# PIC18_Peripheral_breakout_LRbuttons.net
KiCad netlist of a schematic drawn in EAGLE
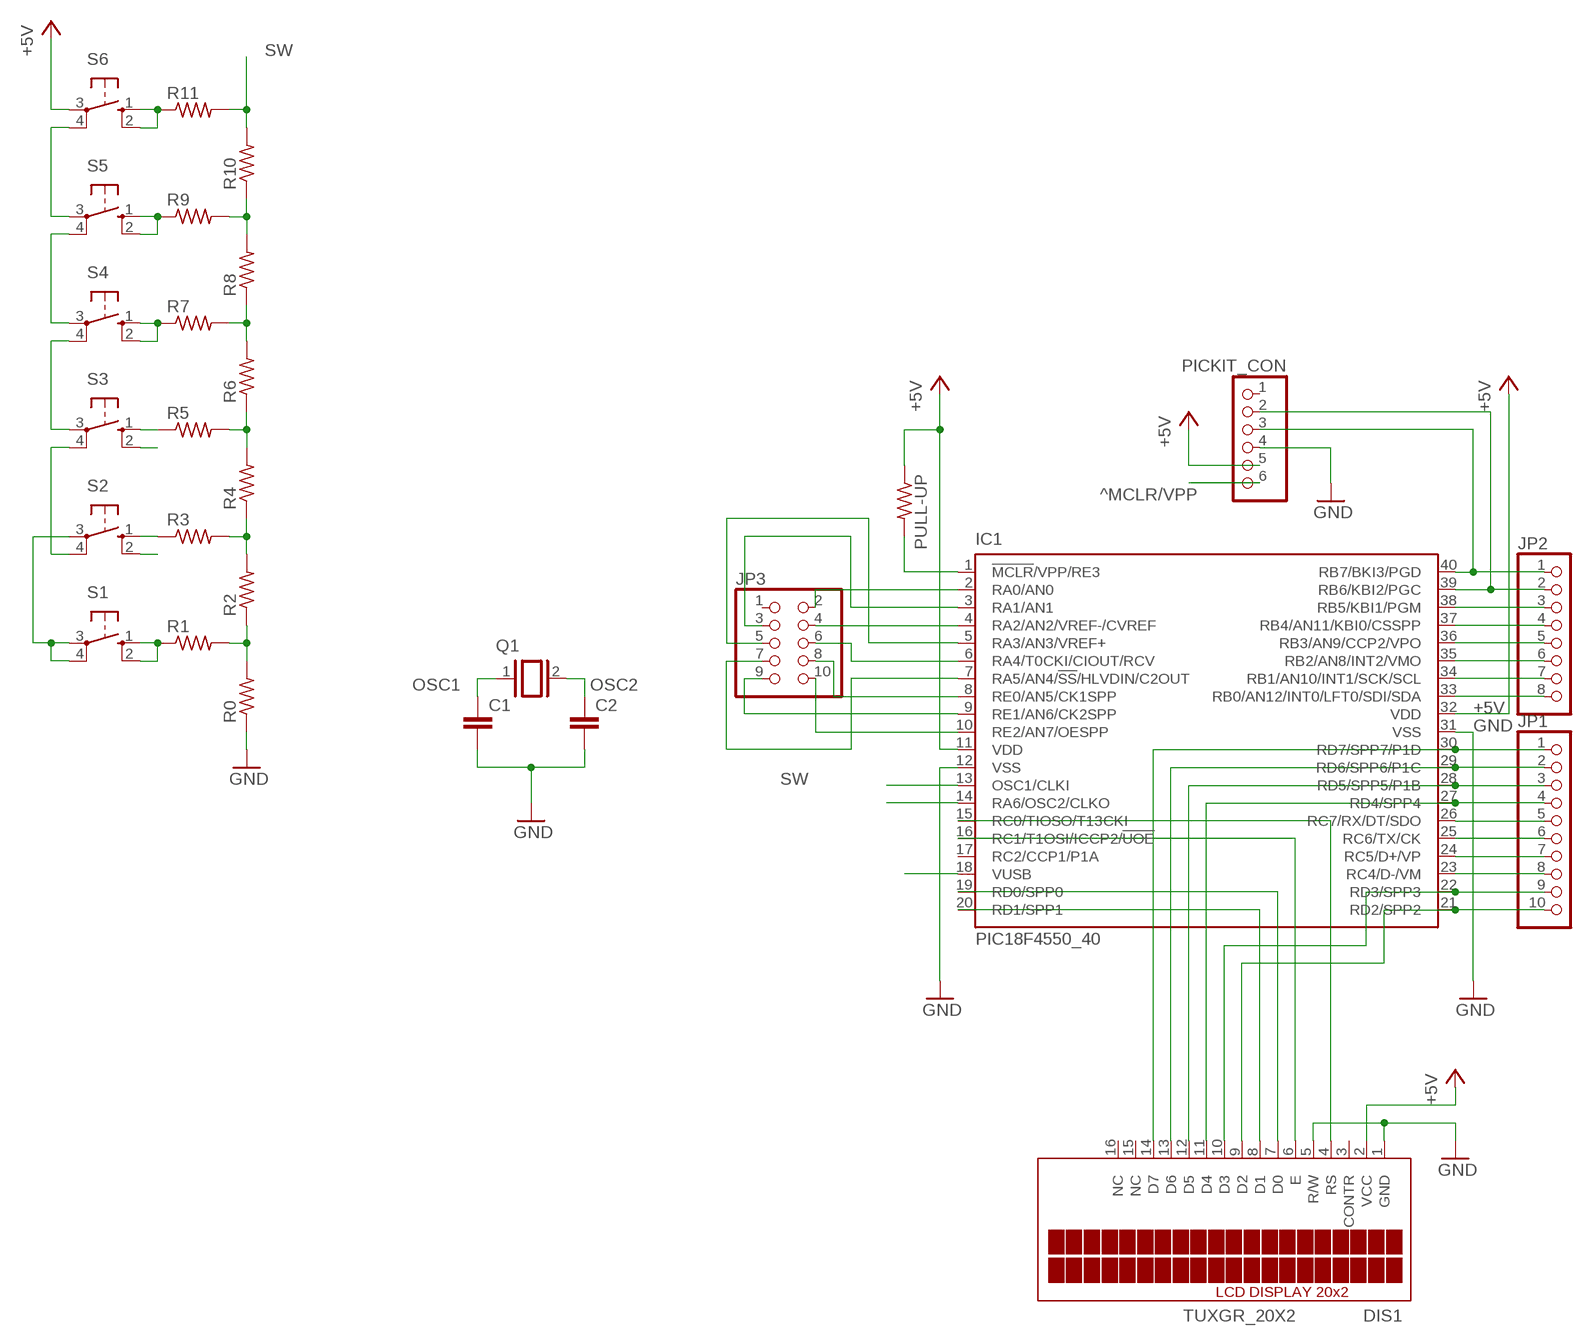
[diagram p0: schematic, sheet 1]

(export (version "E")
  (design (tool "Eeschema 10.0.6"))
  (components
    (comp (ref "C1")
      (value "C-EUC1206")
      (footprint "eagle-import:C1206")
      (libsource (lib "eagle-import") (part "C-EUC1206"))
    )
    (comp (ref "C2")
      (value "C-EUC1206")
      (footprint "eagle-import:C1206")
      (libsource (lib "eagle-import") (part "C-EUC1206"))
    )
    (comp (ref "DIS1")
      (value "TUXGR_20X2")
      (footprint "eagle-import:TUXGR_20X2")
      (libsource (lib "eagle-import") (part "TUXGR_20X2"))
    )
    (comp (ref "IC1")
      (value "PIC18F4550_40")
      (footprint "eagle-import:DIL40")
      (fields (field (name "MF") "MICROCHIP") (field (name "MPN") "PIC18F4550-I/P"))
      (libsource (lib "eagle-import") (part "PIC18F4_40550"))
    )
    (comp (ref "JP1")
      (value "PINHD-1X10")
      (footprint "eagle-import:1X10")
      (libsource (lib "eagle-import") (part "PINHD-1X10"))
    )
    (comp (ref "JP2")
      (value "PINHD-1X8")
      (footprint "eagle-import:1X08")
      (libsource (lib "eagle-import") (part "PINHD-1X8"))
    )
    (comp (ref "JP3")
      (value "PINHD-2X5")
      (footprint "eagle-import:2X05")
      (libsource (lib "eagle-import") (part "PINHD-2X5"))
    )
    (comp (ref "PICKIT_CON")
      (value "PINHD-1X6/90")
      (footprint "eagle-import:1X06_90")
      (libsource (lib "eagle-import") (part "PINHD-1X6/90"))
    )
    (comp (ref "PULL-UP")
      (value "R-US_R1206")
      (footprint "eagle-import:R1206")
      (libsource (lib "eagle-import") (part "R-US_R1206"))
    )
    (comp (ref "Q1")
      (value "XTAL/S")
      (footprint "eagle-import:QS")
      (libsource (lib "eagle-import") (part "XTAL/S"))
    )
    (comp (ref "R0")
      (value "R-US_R1206")
      (footprint "eagle-import:R1206")
      (libsource (lib "eagle-import") (part "R-US_R1206"))
    )
    (comp (ref "R1")
      (value "R-US_R1206")
      (footprint "eagle-import:R1206")
      (libsource (lib "eagle-import") (part "R-US_R1206"))
    )
    (comp (ref "R2")
      (value "R-US_R1206")
      (footprint "eagle-import:R1206")
      (libsource (lib "eagle-import") (part "R-US_R1206"))
    )
    (comp (ref "R3")
      (value "R-US_R1206")
      (footprint "eagle-import:R1206")
      (libsource (lib "eagle-import") (part "R-US_R1206"))
    )
    (comp (ref "R4")
      (value "R-US_R1206")
      (footprint "eagle-import:R1206")
      (libsource (lib "eagle-import") (part "R-US_R1206"))
    )
    (comp (ref "R5")
      (value "R-US_R1206")
      (footprint "eagle-import:R1206")
      (libsource (lib "eagle-import") (part "R-US_R1206"))
    )
    (comp (ref "R6")
      (value "R-US_R1206")
      (footprint "eagle-import:R1206")
      (libsource (lib "eagle-import") (part "R-US_R1206"))
    )
    (comp (ref "R7")
      (value "R-US_R1206")
      (footprint "eagle-import:R1206")
      (libsource (lib "eagle-import") (part "R-US_R1206"))
    )
    (comp (ref "R8")
      (value "R-US_R1206")
      (footprint "eagle-import:R1206")
      (libsource (lib "eagle-import") (part "R-US_R1206"))
    )
    (comp (ref "R9")
      (value "R-US_R1206")
      (footprint "eagle-import:R1206")
      (libsource (lib "eagle-import") (part "R-US_R1206"))
    )
    (comp (ref "R10")
      (value "R-US_R1206")
      (footprint "eagle-import:R1206")
      (libsource (lib "eagle-import") (part "R-US_R1206"))
    )
    (comp (ref "R11")
      (value "R-US_R1206")
      (footprint "eagle-import:R1206")
      (libsource (lib "eagle-import") (part "R-US_R1206"))
    )
    (comp (ref "S1")
      (value "10-XX")
      (footprint "eagle-import:B3F-10XX")
      (fields (field (name "MPN") "B3F-1000"))
      (libsource (lib "eagle-import") (part "10-XX"))
    )
    (comp (ref "S2")
      (value "10-XX")
      (footprint "eagle-import:B3F-10XX")
      (fields (field (name "MPN") "B3F-1000"))
      (libsource (lib "eagle-import") (part "10-XX"))
    )
    (comp (ref "S3")
      (value "10-XX")
      (footprint "eagle-import:B3F-10XX")
      (fields (field (name "MPN") "B3F-1000"))
      (libsource (lib "eagle-import") (part "10-XX"))
    )
    (comp (ref "S4")
      (value "10-XX")
      (footprint "eagle-import:B3F-10XX")
      (fields (field (name "MPN") "B3F-1000"))
      (libsource (lib "eagle-import") (part "10-XX"))
    )
    (comp (ref "S5")
      (value "10-XX")
      (footprint "eagle-import:B3F-10XX")
      (fields (field (name "MPN") "B3F-1000"))
      (libsource (lib "eagle-import") (part "10-XX"))
    )
    (comp (ref "S6")
      (value "10-XX")
      (footprint "eagle-import:B3F-10XX")
      (fields (field (name "MPN") "B3F-1000"))
      (libsource (lib "eagle-import") (part "10-XX"))
    )
  )
  (nets
    (net (code "1") (name "+5V") (class "Default")
      (node (ref "DIS1") (pin "2") (pinfunction "VCC_2") (pintype "power_in"))
      (node (ref "IC1") (pin "11") (pinfunction "VDD_11") (pintype "power_in"))
      (node (ref "IC1") (pin "32") (pinfunction "VDD_32") (pintype "power_in"))
      (node (ref "PICKIT_CON") (pin "5") (pinfunction "5_5") (pintype "passive"))
      (node (ref "PULL-UP") (pin "1") (pinfunction "1_1") (pintype "passive"))
      (node (ref "S6") (pin "3") (pinfunction "P_3") (pintype "passive"))
    )
    (net (code "2") (name "/OSC1") (class "Default")
      (node (ref "C1") (pin "1") (pinfunction "1_1") (pintype "passive"))
      (node (ref "IC1") (pin "13") (pinfunction "OSC1/CLKI_13") (pintype "input"))
      (node (ref "Q1") (pin "1") (pinfunction "1_1") (pintype "passive"))
    )
    (net (code "3") (name "/OSC2") (class "Default")
      (node (ref "C2") (pin "1") (pinfunction "1_1") (pintype "passive"))
      (node (ref "IC1") (pin "14") (pinfunction "RA6/OSC2/CLKO_14") (pintype "output"))
      (node (ref "Q1") (pin "2") (pinfunction "2_2") (pintype "passive"))
    )
    (net (code "4") (name "/SW") (class "Default")
      (node (ref "IC1") (pin "10") (pinfunction "RE2/AN7/OESPP_10") (pintype "bidirectional"))
      (node (ref "JP3") (pin "10") (pinfunction "10_10") (pintype "passive"))
      (node (ref "R10") (pin "2") (pinfunction "2_2") (pintype "passive"))
      (node (ref "R11") (pin "2") (pinfunction "2_2") (pintype "passive"))
    )
    (net (code "5") (name "/^MCLR{slash}VPP") (class "Default")
      (node (ref "IC1") (pin "1") (pinfunction "~{MCLR}/VPP/RE3_1") (pintype "input"))
      (node (ref "PICKIT_CON") (pin "6") (pinfunction "6_6") (pintype "passive"))
      (node (ref "PULL-UP") (pin "2") (pinfunction "2_2") (pintype "passive"))
    )
    (net (code "6") (name "GND") (class "Default")
      (node (ref "C1") (pin "2") (pinfunction "2_2") (pintype "passive"))
      (node (ref "C2") (pin "2") (pinfunction "2_2") (pintype "passive"))
      (node (ref "DIS1") (pin "1") (pinfunction "GND_1") (pintype "power_in"))
      (node (ref "DIS1") (pin "5") (pinfunction "R/W_5") (pintype "input"))
      (node (ref "IC1") (pin "12") (pinfunction "VSS_12") (pintype "power_in"))
      (node (ref "IC1") (pin "31") (pinfunction "VSS_31") (pintype "power_in"))
      (node (ref "PICKIT_CON") (pin "4") (pinfunction "4_4") (pintype "passive"))
      (node (ref "R0") (pin "1") (pinfunction "1_1") (pintype "passive"))
    )
    (net (code "7") (name "Net-(DIS1-D0)") (class "Default")
      (node (ref "DIS1") (pin "7") (pinfunction "D0_7") (pintype "input"))
      (node (ref "IC1") (pin "19") (pinfunction "RD0/SPP0_19") (pintype "bidirectional"))
    )
    (net (code "8") (name "Net-(DIS1-D1)") (class "Default")
      (node (ref "DIS1") (pin "8") (pinfunction "D1_8") (pintype "input"))
      (node (ref "IC1") (pin "20") (pinfunction "RD1/SPP1_20") (pintype "bidirectional"))
    )
    (net (code "9") (name "Net-(DIS1-D2)") (class "Default")
      (node (ref "DIS1") (pin "9") (pinfunction "D2_9") (pintype "input"))
      (node (ref "IC1") (pin "21") (pinfunction "RD2/SPP2_21") (pintype "bidirectional"))
      (node (ref "JP1") (pin "10") (pinfunction "10_10") (pintype "passive"))
    )
    (net (code "10") (name "Net-(DIS1-D3)") (class "Default")
      (node (ref "DIS1") (pin "10") (pinfunction "D3_10") (pintype "input"))
      (node (ref "IC1") (pin "22") (pinfunction "RD3/SPP3_22") (pintype "bidirectional"))
      (node (ref "JP1") (pin "9") (pinfunction "9_9") (pintype "passive"))
    )
    (net (code "11") (name "Net-(DIS1-D4)") (class "Default")
      (node (ref "DIS1") (pin "11") (pinfunction "D4_11") (pintype "input"))
      (node (ref "IC1") (pin "27") (pinfunction "RD4/SPP4_27") (pintype "bidirectional"))
      (node (ref "JP1") (pin "4") (pinfunction "4_4") (pintype "passive"))
    )
    (net (code "12") (name "Net-(DIS1-D5)") (class "Default")
      (node (ref "DIS1") (pin "12") (pinfunction "D5_12") (pintype "input"))
      (node (ref "IC1") (pin "28") (pinfunction "RD5/SPP5/P1B_28") (pintype "bidirectional"))
      (node (ref "JP1") (pin "3") (pinfunction "3_3") (pintype "passive"))
    )
    (net (code "13") (name "Net-(DIS1-D6)") (class "Default")
      (node (ref "DIS1") (pin "13") (pinfunction "D6_13") (pintype "input"))
      (node (ref "IC1") (pin "29") (pinfunction "RD6/SPP6/P1C_29") (pintype "bidirectional"))
      (node (ref "JP1") (pin "2") (pinfunction "2_2") (pintype "passive"))
    )
    (net (code "14") (name "Net-(DIS1-D7)") (class "Default")
      (node (ref "DIS1") (pin "14") (pinfunction "D7_14") (pintype "input"))
      (node (ref "IC1") (pin "30") (pinfunction "RD7/SPP7/P1D_30") (pintype "bidirectional"))
      (node (ref "JP1") (pin "1") (pinfunction "1_1") (pintype "passive"))
    )
    (net (code "15") (name "Net-(DIS1-E)") (class "Default")
      (node (ref "DIS1") (pin "6") (pinfunction "E_6") (pintype "input"))
      (node (ref "IC1") (pin "16") (pinfunction "RC1/T1OSI/ICCP2/~{UOE}_16") (pintype "bidirectional"))
    )
    (net (code "16") (name "Net-(DIS1-RS)") (class "Default")
      (node (ref "DIS1") (pin "4") (pinfunction "RS_4") (pintype "input"))
      (node (ref "IC1") (pin "15") (pinfunction "RC0/TIOSO/T13CKI_15") (pintype "bidirectional"))
    )
    (net (code "17") (name "Net-(IC1-RA0{slash}AN0)") (class "Default")
      (node (ref "IC1") (pin "2") (pinfunction "RA0/AN0_2") (pintype "bidirectional"))
      (node (ref "JP3") (pin "2") (pinfunction "2_2") (pintype "passive"))
    )
    (net (code "18") (name "Net-(IC1-RA1{slash}AN1)") (class "Default")
      (node (ref "IC1") (pin "3") (pinfunction "RA1/AN1_3") (pintype "bidirectional"))
      (node (ref "JP3") (pin "3") (pinfunction "3_3") (pintype "passive"))
    )
    (net (code "19") (name "Net-(IC1-RA2{slash}AN2{slash}VREF-{slash}CVREF)") (class "Default")
      (node (ref "IC1") (pin "4") (pinfunction "RA2/AN2/VREF-/CVREF_4") (pintype "bidirectional"))
      (node (ref "JP3") (pin "4") (pinfunction "4_4") (pintype "passive"))
    )
    (net (code "20") (name "Net-(IC1-RA3{slash}AN3{slash}VREF+)") (class "Default")
      (node (ref "IC1") (pin "5") (pinfunction "RA3/AN3/VREF+_5") (pintype "bidirectional"))
      (node (ref "JP3") (pin "5") (pinfunction "5_5") (pintype "passive"))
    )
    (net (code "21") (name "Net-(IC1-RA4{slash}T0CKI{slash}CIOUT{slash}RCV)") (class "Default")
      (node (ref "IC1") (pin "6") (pinfunction "RA4/T0CKI/CIOUT/RCV_6") (pintype "bidirectional"))
      (node (ref "JP3") (pin "6") (pinfunction "6_6") (pintype "passive"))
    )
    (net (code "22") (name "Net-(IC1-RA5{slash}AN4{slash}~{SS}{slash}HLVDIN{slash}C2OUT)") (class "Default")
      (node (ref "IC1") (pin "7") (pinfunction "RA5/AN4/~{SS}/HLVDIN/C2OUT_7") (pintype "bidirectional"))
      (node (ref "JP3") (pin "7") (pinfunction "7_7") (pintype "passive"))
    )
    (net (code "23") (name "Net-(IC1-RB0{slash}AN12{slash}INT0{slash}LFT0{slash}SDI{slash}SDA)") (class "Default")
      (node (ref "IC1") (pin "33") (pinfunction "RB0/AN12/INT0/LFT0/SDI/SDA_33") (pintype "bidirectional"))
      (node (ref "JP2") (pin "8") (pinfunction "8_8") (pintype "passive"))
    )
    (net (code "24") (name "Net-(IC1-RB1{slash}AN10{slash}INT1{slash}SCK{slash}SCL)") (class "Default")
      (node (ref "IC1") (pin "34") (pinfunction "RB1/AN10/INT1/SCK/SCL_34") (pintype "bidirectional"))
      (node (ref "JP2") (pin "7") (pinfunction "7_7") (pintype "passive"))
    )
    (net (code "25") (name "Net-(IC1-RB2{slash}AN8{slash}INT2{slash}VMO)") (class "Default")
      (node (ref "IC1") (pin "35") (pinfunction "RB2/AN8/INT2/VMO_35") (pintype "bidirectional"))
      (node (ref "JP2") (pin "6") (pinfunction "6_6") (pintype "passive"))
    )
    (net (code "26") (name "Net-(IC1-RB3{slash}AN9{slash}CCP2{slash}VPO)") (class "Default")
      (node (ref "IC1") (pin "36") (pinfunction "RB3/AN9/CCP2/VPO_36") (pintype "bidirectional"))
      (node (ref "JP2") (pin "5") (pinfunction "5_5") (pintype "passive"))
    )
    (net (code "27") (name "Net-(IC1-RB4{slash}AN11{slash}KBI0{slash}CSSPP)") (class "Default")
      (node (ref "IC1") (pin "37") (pinfunction "RB4/AN11/KBI0/CSSPP_37") (pintype "bidirectional"))
      (node (ref "JP2") (pin "4") (pinfunction "4_4") (pintype "passive"))
    )
    (net (code "28") (name "Net-(IC1-RB5{slash}KBI1{slash}PGM)") (class "Default")
      (node (ref "IC1") (pin "38") (pinfunction "RB5/KBI1/PGM_38") (pintype "bidirectional"))
      (node (ref "JP2") (pin "3") (pinfunction "3_3") (pintype "passive"))
    )
    (net (code "29") (name "Net-(IC1-RB6{slash}KBI2{slash}PGC)") (class "Default")
      (node (ref "IC1") (pin "39") (pinfunction "RB6/KBI2/PGC_39") (pintype "bidirectional"))
      (node (ref "JP2") (pin "2") (pinfunction "2_2") (pintype "passive"))
      (node (ref "PICKIT_CON") (pin "2") (pinfunction "2_2") (pintype "passive"))
    )
    (net (code "30") (name "Net-(IC1-RB7{slash}BKI3{slash}PGD)") (class "Default")
      (node (ref "IC1") (pin "40") (pinfunction "RB7/BKI3/PGD_40") (pintype "bidirectional"))
      (node (ref "JP2") (pin "1") (pinfunction "1_1") (pintype "passive"))
      (node (ref "PICKIT_CON") (pin "3") (pinfunction "3_3") (pintype "passive"))
    )
    (net (code "31") (name "Net-(IC1-RC4{slash}D-{slash}VM)") (class "Default")
      (node (ref "IC1") (pin "23") (pinfunction "RC4/D-/VM_23") (pintype "bidirectional"))
      (node (ref "JP1") (pin "8") (pinfunction "8_8") (pintype "passive"))
    )
    (net (code "32") (name "Net-(IC1-RC5{slash}D+{slash}VP)") (class "Default")
      (node (ref "IC1") (pin "24") (pinfunction "RC5/D+/VP_24") (pintype "bidirectional"))
      (node (ref "JP1") (pin "7") (pinfunction "7_7") (pintype "passive"))
    )
    (net (code "33") (name "Net-(IC1-RC6{slash}TX{slash}CK)") (class "Default")
      (node (ref "IC1") (pin "25") (pinfunction "RC6/TX/CK_25") (pintype "bidirectional"))
      (node (ref "JP1") (pin "6") (pinfunction "6_6") (pintype "passive"))
    )
    (net (code "34") (name "Net-(IC1-RC7{slash}RX{slash}DT{slash}SDO)") (class "Default")
      (node (ref "IC1") (pin "26") (pinfunction "RC7/RX/DT/SDO_26") (pintype "bidirectional"))
      (node (ref "JP1") (pin "5") (pinfunction "5_5") (pintype "passive"))
    )
    (net (code "35") (name "Net-(IC1-RE0{slash}AN5{slash}CK1SPP)") (class "Default")
      (node (ref "IC1") (pin "8") (pinfunction "RE0/AN5/CK1SPP_8") (pintype "bidirectional"))
      (node (ref "JP3") (pin "8") (pinfunction "8_8") (pintype "passive"))
    )
    (net (code "36") (name "Net-(IC1-RE1{slash}AN6{slash}CK2SPP)") (class "Default")
      (node (ref "IC1") (pin "9") (pinfunction "RE1/AN6/CK2SPP_9") (pintype "bidirectional"))
      (node (ref "JP3") (pin "9") (pinfunction "9_9") (pintype "passive"))
    )
    (net (code "37") (name "Net-(R0-Pad2)") (class "Default")
      (node (ref "R0") (pin "2") (pinfunction "2_2") (pintype "passive"))
      (node (ref "R1") (pin "2") (pinfunction "2_2") (pintype "passive"))
      (node (ref "R2") (pin "1") (pinfunction "1_1") (pintype "passive"))
    )
    (net (code "38") (name "Net-(R2-Pad2)") (class "Default")
      (node (ref "R2") (pin "2") (pinfunction "2_2") (pintype "passive"))
      (node (ref "R3") (pin "2") (pinfunction "2_2") (pintype "passive"))
      (node (ref "R4") (pin "1") (pinfunction "1_1") (pintype "passive"))
    )
    (net (code "39") (name "Net-(R4-Pad2)") (class "Default")
      (node (ref "R4") (pin "2") (pinfunction "2_2") (pintype "passive"))
      (node (ref "R5") (pin "2") (pinfunction "2_2") (pintype "passive"))
      (node (ref "R6") (pin "1") (pinfunction "1_1") (pintype "passive"))
    )
    (net (code "40") (name "Net-(R6-Pad2)") (class "Default")
      (node (ref "R6") (pin "2") (pinfunction "2_2") (pintype "passive"))
      (node (ref "R7") (pin "2") (pinfunction "2_2") (pintype "passive"))
      (node (ref "R8") (pin "1") (pinfunction "1_1") (pintype "passive"))
    )
    (net (code "41") (name "Net-(R10-Pad1)") (class "Default")
      (node (ref "R10") (pin "1") (pinfunction "1_1") (pintype "passive"))
      (node (ref "R8") (pin "2") (pinfunction "2_2") (pintype "passive"))
      (node (ref "R9") (pin "2") (pinfunction "2_2") (pintype "passive"))
    )
    (net (code "42") (name "Net-(S1-P)") (class "Default")
      (node (ref "S1") (pin "3") (pinfunction "P_3") (pintype "passive"))
      (node (ref "S1") (pin "4") (pinfunction "P1_4") (pintype "passive"))
      (node (ref "S2") (pin "3") (pinfunction "P_3") (pintype "passive"))
    )
    (net (code "43") (name "Net-(S1-S)") (class "Default")
      (node (ref "R1") (pin "1") (pinfunction "1_1") (pintype "passive"))
      (node (ref "S1") (pin "1") (pinfunction "S_1") (pintype "passive"))
      (node (ref "S1") (pin "2") (pinfunction "S1_2") (pintype "passive"))
    )
    (net (code "44") (name "Net-(S2-P1)") (class "Default")
      (node (ref "S2") (pin "4") (pinfunction "P1_4") (pintype "passive"))
      (node (ref "S3") (pin "4") (pinfunction "P1_4") (pintype "passive"))
    )
    (net (code "45") (name "Net-(S2-S)") (class "Default")
      (node (ref "R3") (pin "1") (pinfunction "1_1") (pintype "passive"))
      (node (ref "S2") (pin "1") (pinfunction "S_1") (pintype "passive"))
    )
    (net (code "46") (name "Net-(S3-P)") (class "Default")
      (node (ref "S3") (pin "3") (pinfunction "P_3") (pintype "passive"))
      (node (ref "S4") (pin "4") (pinfunction "P1_4") (pintype "passive"))
    )
    (net (code "47") (name "Net-(S3-S)") (class "Default")
      (node (ref "R5") (pin "1") (pinfunction "1_1") (pintype "passive"))
      (node (ref "S3") (pin "1") (pinfunction "S_1") (pintype "passive"))
    )
    (net (code "48") (name "Net-(S4-P)") (class "Default")
      (node (ref "S4") (pin "3") (pinfunction "P_3") (pintype "passive"))
      (node (ref "S5") (pin "4") (pinfunction "P1_4") (pintype "passive"))
    )
    (net (code "49") (name "Net-(S4-S)") (class "Default")
      (node (ref "R7") (pin "1") (pinfunction "1_1") (pintype "passive"))
      (node (ref "S4") (pin "1") (pinfunction "S_1") (pintype "passive"))
      (node (ref "S4") (pin "2") (pinfunction "S1_2") (pintype "passive"))
    )
    (net (code "50") (name "Net-(S5-P)") (class "Default")
      (node (ref "S5") (pin "3") (pinfunction "P_3") (pintype "passive"))
      (node (ref "S6") (pin "4") (pinfunction "P1_4") (pintype "passive"))
    )
    (net (code "51") (name "Net-(S5-S)") (class "Default")
      (node (ref "R9") (pin "1") (pinfunction "1_1") (pintype "passive"))
      (node (ref "S5") (pin "1") (pinfunction "S_1") (pintype "passive"))
      (node (ref "S5") (pin "2") (pinfunction "S1_2") (pintype "passive"))
    )
    (net (code "52") (name "Net-(S6-S)") (class "Default")
      (node (ref "R11") (pin "1") (pinfunction "1_1") (pintype "passive"))
      (node (ref "S6") (pin "1") (pinfunction "S_1") (pintype "passive"))
      (node (ref "S6") (pin "2") (pinfunction "S1_2") (pintype "passive"))
    )
    (net (code "53") (name "unconnected-(DIS1-CONTR-Pad3)") (class "Default")
      (node (ref "DIS1") (pin "3") (pinfunction "CONTR_3") (pintype "input"))
    )
    (net (code "54") (name "unconnected-(DIS1-NC-Pad15)") (class "Default")
      (node (ref "DIS1") (pin "15") (pinfunction "NC_15") (pintype "no_connect"))
    )
    (net (code "55") (name "unconnected-(DIS1-NC-Pad16)") (class "Default")
      (node (ref "DIS1") (pin "16") (pinfunction "NC_16") (pintype "no_connect"))
    )
    (net (code "56") (name "unconnected-(IC1-RC2{slash}CCP1{slash}P1A-Pad17)") (class "Default")
      (node (ref "IC1") (pin "17") (pinfunction "RC2/CCP1/P1A_17") (pintype "bidirectional"))
    )
    (net (code "57") (name "unconnected-(IC1-VUSB-Pad18)") (class "Default")
      (node (ref "IC1") (pin "18") (pinfunction "VUSB_18") (pintype "bidirectional"))
    )
    (net (code "58") (name "unconnected-(JP3-Pad1)") (class "Default")
      (node (ref "JP3") (pin "1") (pinfunction "1_1") (pintype "passive"))
    )
    (net (code "59") (name "unconnected-(PICKIT_CON-Pad1)") (class "Default")
      (node (ref "PICKIT_CON") (pin "1") (pinfunction "1_1") (pintype "passive"))
    )
    (net (code "60") (name "unconnected-(S2-S1-Pad2)") (class "Default")
      (node (ref "S2") (pin "2") (pinfunction "S1_2") (pintype "passive"))
    )
    (net (code "61") (name "unconnected-(S3-S1-Pad2)") (class "Default")
      (node (ref "S3") (pin "2") (pinfunction "S1_2") (pintype "passive"))
    )
  )
)
